# above_water_attachment.net
KiCad netlist of a schematic drawn in EAGLE
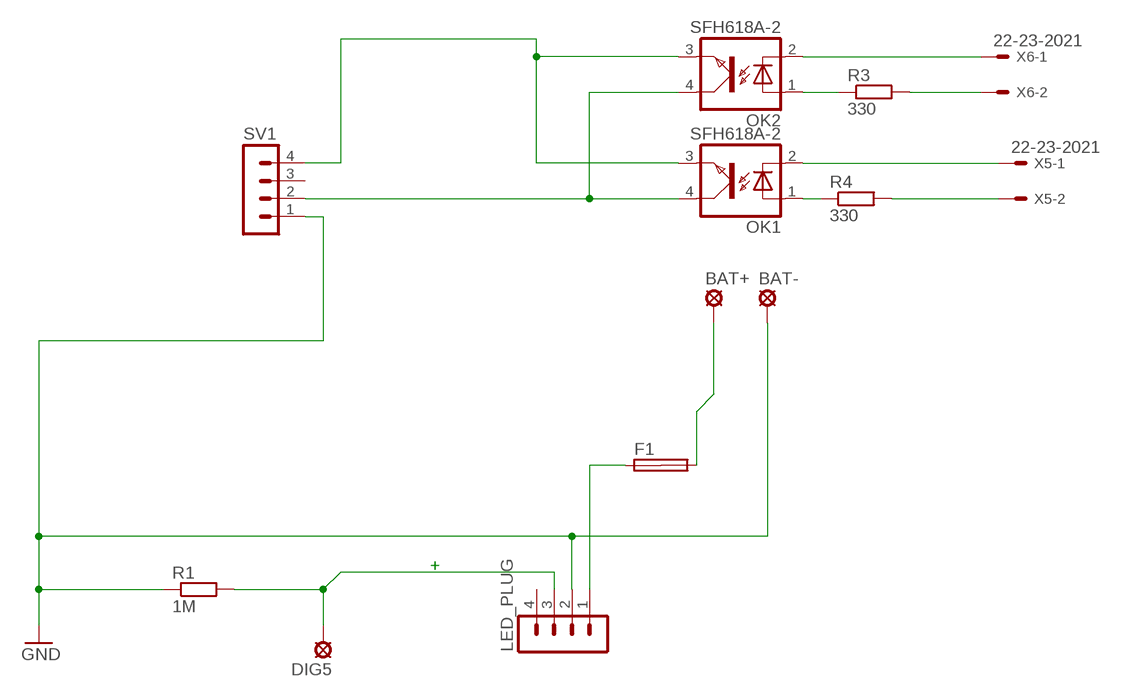
[diagram p0: schematic, sheet 1]

(export (version "E")
  (design (tool "Eeschema 10.0.6"))
  (components
    (comp (ref "BAT+")
      (value "bat+")
      (footprint "eagle-import:SE14")
      (libsource (lib "eagle-import") (part "SE14"))
    )
    (comp (ref "BAT-")
      (value "Bat-")
      (footprint "eagle-import:SE14")
      (libsource (lib "eagle-import") (part "SE14"))
    )
    (comp (ref "DIG5")
      (value "Led-")
      (footprint "eagle-import:SE14")
      (libsource (lib "eagle-import") (part "SE14"))
    )
    (comp (ref "F1")
      (value "SHK20Q")
      (footprint "eagle-import:SHK20Q")
      (libsource (lib "eagle-import") (part "SHK20Q"))
    )
    (comp (ref "LED_PLUG")
      (value "MA04-1")
      (footprint "eagle-import:MA04-1")
      (libsource (lib "eagle-import") (part "MA04-1"))
    )
    (comp (ref "OK1")
      (value "SFH618A-2")
      (footprint "eagle-import:DIP4")
      (fields (field (name "MF") "VISHAY/TELEFUNKEN"))
      (libsource (lib "eagle-import") (part "SFH618?A-2"))
    )
    (comp (ref "OK2")
      (value "SFH618A-2")
      (footprint "eagle-import:DIP4")
      (fields (field (name "MF") "VISHAY/TELEFUNKEN"))
      (libsource (lib "eagle-import") (part "SFH618?A-2"))
    )
    (comp (ref "R1")
      (value "1M")
      (footprint "eagle-import:R2512")
      (libsource (lib "eagle-import") (part "R-EU_R2512"))
    )
    (comp (ref "R3")
      (value "330")
      (footprint "eagle-import:R1206")
      (libsource (lib "eagle-import") (part "R-EU_R1206"))
    )
    (comp (ref "R4")
      (value "330")
      (footprint "eagle-import:R1206")
      (libsource (lib "eagle-import") (part "R-EU_R1206"))
    )
    (comp (ref "SV1")
      (value "MA04-1")
      (footprint "eagle-import:MA04-1")
      (libsource (lib "eagle-import") (part "MA04-1"))
    )
    (comp (ref "X5")
      (value "22-23-2021")
      (footprint "eagle-import:22-23-2021")
      (fields (field (name "MF") "MOLEX"))
      (libsource (lib "eagle-import") (part "22-23-2021"))
    )
    (comp (ref "X6")
      (value "22-23-2021")
      (footprint "eagle-import:22-23-2021")
      (fields (field (name "MF") "MOLEX"))
      (libsource (lib "eagle-import") (part "22-23-2021"))
    )
  )
  (nets
    (net (code "1") (name "GND") (class "Default")
      (node (ref "BAT-") (pin "MP") (pinfunction "MP_MP") (pintype "passive"))
      (node (ref "LED_PLUG") (pin "2") (pinfunction "2_2") (pintype "passive"))
      (node (ref "R1") (pin "1") (pinfunction "1_1") (pintype "passive"))
      (node (ref "SV1") (pin "1") (pinfunction "1_1") (pintype "passive"))
    )
    (net (code "2") (name "Net-(BAT+-PadMP)") (class "Default")
      (node (ref "BAT+") (pin "MP") (pinfunction "MP_MP") (pintype "passive"))
      (node (ref "F1") (pin "2A") (pinfunction "2A_2A") (pintype "passive"))
    )
    (net (code "3") (name "Net-(DIG5-PadMP)") (class "Default")
      (node (ref "DIG5") (pin "MP") (pinfunction "MP_MP") (pintype "passive"))
      (node (ref "LED_PLUG") (pin "3") (pinfunction "3_3") (pintype "passive"))
      (node (ref "R1") (pin "2") (pinfunction "2_2") (pintype "passive"))
    )
    (net (code "4") (name "Net-(F1-Pad1A)") (class "Default")
      (node (ref "F1") (pin "1A") (pinfunction "1A_1A") (pintype "passive"))
      (node (ref "LED_PLUG") (pin "1") (pinfunction "1_1") (pintype "passive"))
    )
    (net (code "5") (name "Net-(OK1-A)") (class "Default")
      (node (ref "OK1") (pin "1") (pinfunction "A_1") (pintype "passive"))
      (node (ref "R4") (pin "1") (pinfunction "1_1") (pintype "passive"))
    )
    (net (code "6") (name "Net-(OK1-C)") (class "Default")
      (node (ref "OK1") (pin "2") (pinfunction "C_2") (pintype "passive"))
      (node (ref "X5") (pin "1") (pinfunction "S_1") (pintype "passive"))
    )
    (net (code "7") (name "Net-(OK1-COL)") (class "Default")
      (node (ref "OK1") (pin "4") (pinfunction "COL_4") (pintype "passive"))
      (node (ref "OK2") (pin "4") (pinfunction "COL_4") (pintype "passive"))
      (node (ref "SV1") (pin "2") (pinfunction "2_2") (pintype "passive"))
    )
    (net (code "8") (name "Net-(OK1-EMIT)") (class "Default")
      (node (ref "OK1") (pin "3") (pinfunction "EMIT_3") (pintype "passive"))
      (node (ref "OK2") (pin "3") (pinfunction "EMIT_3") (pintype "passive"))
      (node (ref "SV1") (pin "4") (pinfunction "4_4") (pintype "passive"))
    )
    (net (code "9") (name "Net-(OK2-A)") (class "Default")
      (node (ref "OK2") (pin "1") (pinfunction "A_1") (pintype "passive"))
      (node (ref "R3") (pin "1") (pinfunction "1_1") (pintype "passive"))
    )
    (net (code "10") (name "Net-(OK2-C)") (class "Default")
      (node (ref "OK2") (pin "2") (pinfunction "C_2") (pintype "passive"))
      (node (ref "X6") (pin "1") (pinfunction "S_1") (pintype "passive"))
    )
    (net (code "11") (name "Net-(X5B-S)") (class "Default")
      (node (ref "R4") (pin "2") (pinfunction "2_2") (pintype "passive"))
      (node (ref "X5") (pin "2") (pinfunction "S_2") (pintype "passive"))
    )
    (net (code "12") (name "Net-(X6B-S)") (class "Default")
      (node (ref "R3") (pin "2") (pinfunction "2_2") (pintype "passive"))
      (node (ref "X6") (pin "2") (pinfunction "S_2") (pintype "passive"))
    )
    (net (code "13") (name "unconnected-(F1-Pad1B)") (class "Default")
      (node (ref "F1") (pin "1B") (pinfunction "1B_1B") (pintype "passive"))
    )
    (net (code "14") (name "unconnected-(F1-Pad2B)") (class "Default")
      (node (ref "F1") (pin "2B") (pinfunction "2B_2B") (pintype "passive"))
    )
    (net (code "15") (name "unconnected-(LED_PLUG-Pad4)") (class "Default")
      (node (ref "LED_PLUG") (pin "4") (pinfunction "4_4") (pintype "passive"))
    )
    (net (code "16") (name "unconnected-(SV1-Pad3)") (class "Default")
      (node (ref "SV1") (pin "3") (pinfunction "3_3") (pintype "passive"))
    )
  )
)
